# PassiveLPG.net
KiCad netlist of a schematic drawn in EAGLE
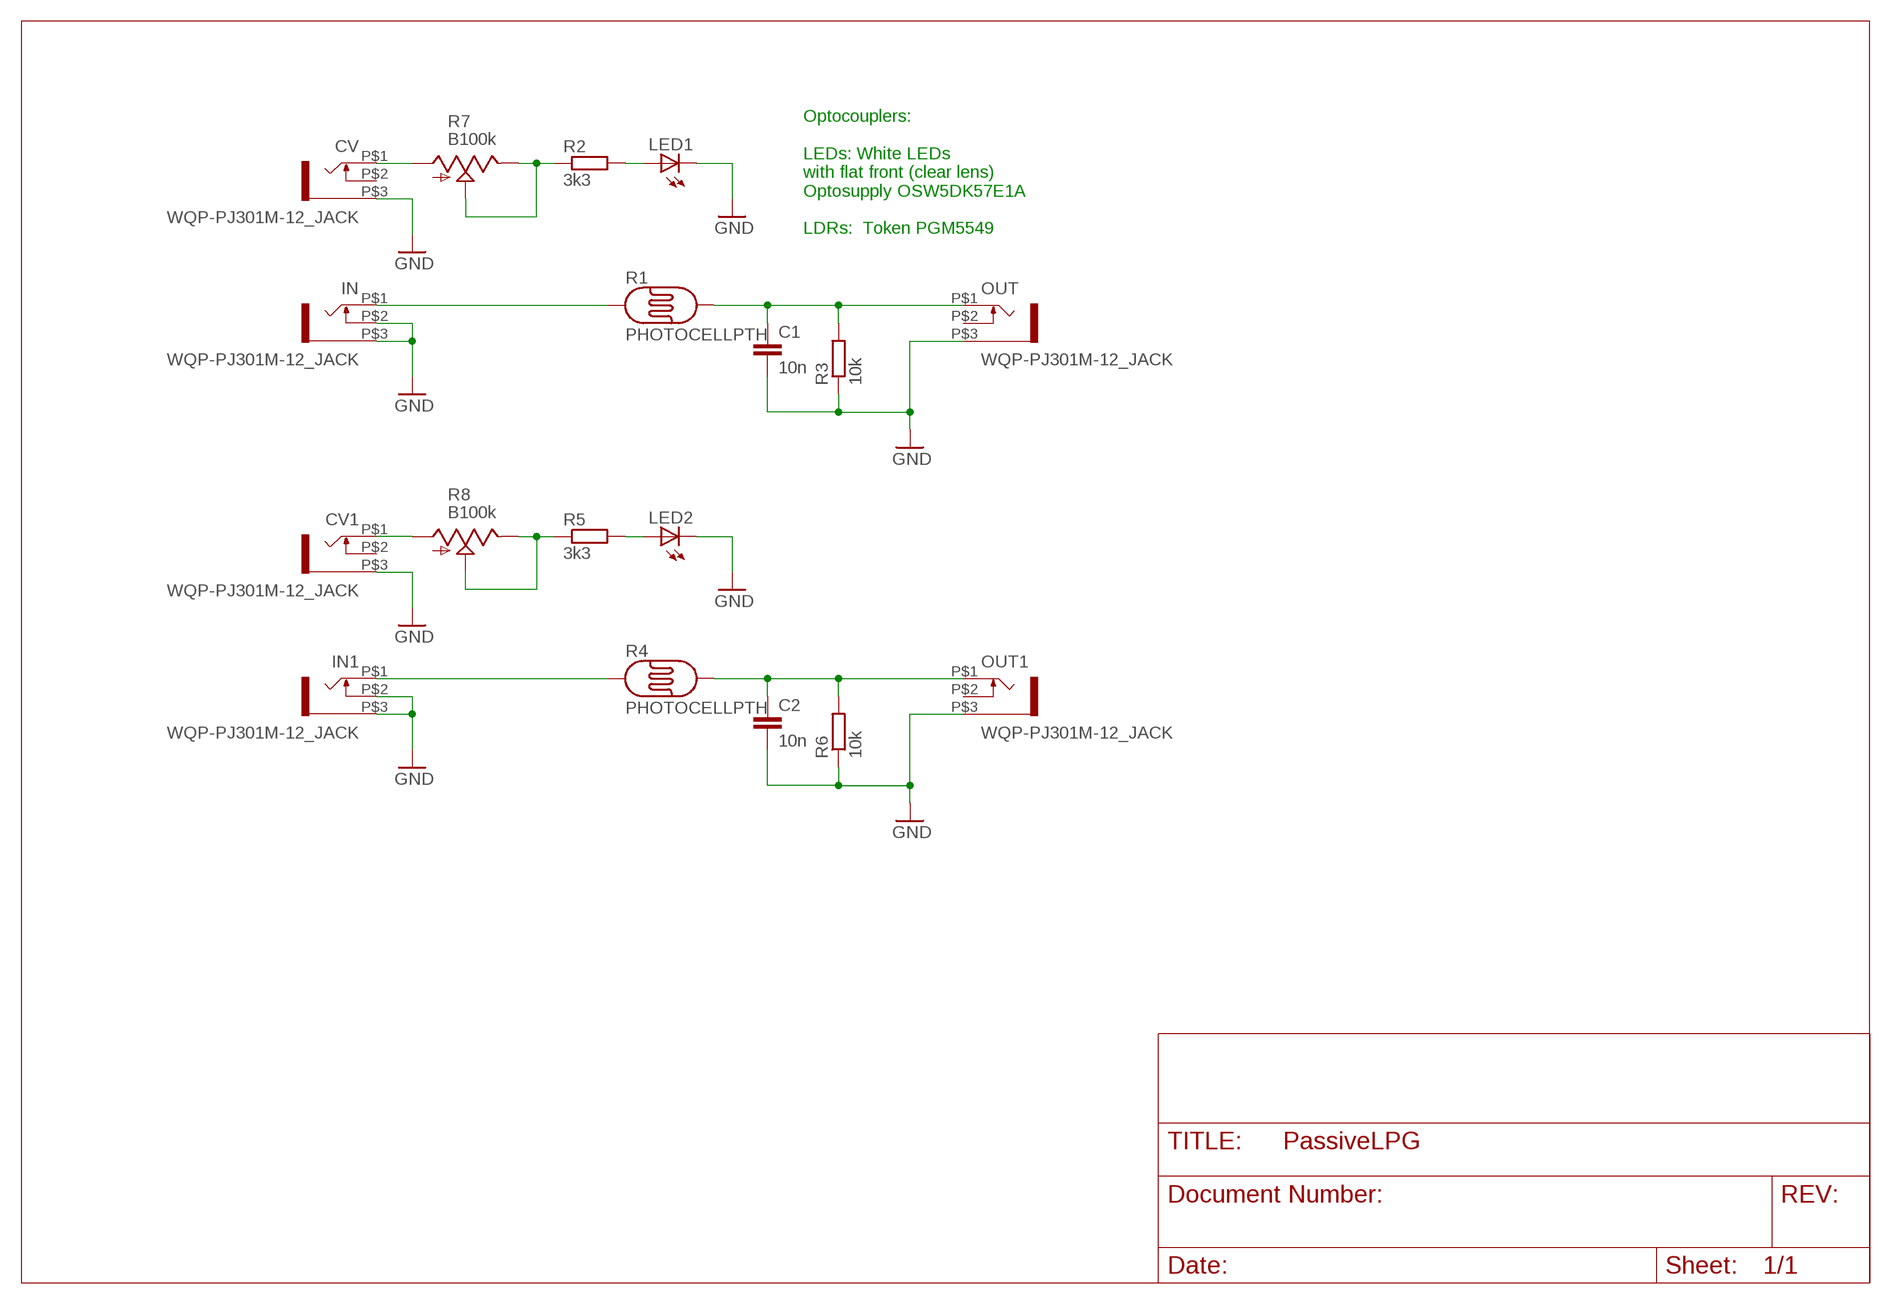
[diagram p0: schematic, sheet 1]

(export (version "E")
  (design (tool "Eeschema 10.0.6"))
  (components
    (comp (ref "C1")
      (value "10n")
      (footprint "eagle-import:C050-025X075")
      (libsource (lib "eagle-import") (part "C-EU050-025X075"))
    )
    (comp (ref "C2")
      (value "10n")
      (footprint "eagle-import:C050-025X075")
      (libsource (lib "eagle-import") (part "C-EU050-025X075"))
    )
    (comp (ref "CV")
      (value "WQP-PJ301M-12_JACK")
      (footprint "eagle-import:WQP-PJ301M-12_JACK")
      (libsource (lib "eagle-import") (part "WQP-PJ301M-12_JACK"))
    )
    (comp (ref "CV1")
      (value "WQP-PJ301M-12_JACK")
      (footprint "eagle-import:WQP-PJ301M-12_JACK")
      (libsource (lib "eagle-import") (part "WQP-PJ301M-12_JACK"))
    )
    (comp (ref "IN")
      (value "WQP-PJ301M-12_JACK")
      (footprint "eagle-import:WQP-PJ301M-12_JACK")
      (libsource (lib "eagle-import") (part "WQP-PJ301M-12_JACK"))
    )
    (comp (ref "IN1")
      (value "WQP-PJ301M-12_JACK")
      (footprint "eagle-import:WQP-PJ301M-12_JACK")
      (libsource (lib "eagle-import") (part "WQP-PJ301M-12_JACK"))
    )
    (comp (ref "LED1")
      (value "LED5MM")
      (footprint "eagle-import:LED5MM")
      (libsource (lib "eagle-import") (part "LED5MM"))
    )
    (comp (ref "LED2")
      (value "LED5MM")
      (footprint "eagle-import:LED5MM")
      (libsource (lib "eagle-import") (part "LED5MM"))
    )
    (comp (ref "OUT")
      (value "WQP-PJ301M-12_JACK")
      (footprint "eagle-import:WQP-PJ301M-12_JACK")
      (libsource (lib "eagle-import") (part "WQP-PJ301M-12_JACK"))
    )
    (comp (ref "OUT1")
      (value "WQP-PJ301M-12_JACK")
      (footprint "eagle-import:WQP-PJ301M-12_JACK")
      (libsource (lib "eagle-import") (part "WQP-PJ301M-12_JACK"))
    )
    (comp (ref "R1")
      (value "PHOTOCELLPTH")
      (footprint "eagle-import:PHOTOCELL")
      (libsource (lib "eagle-import") (part "PHOTOCELLPTH"))
    )
    (comp (ref "R2")
      (value "3k3")
      (footprint "eagle-import:0207_7")
      (libsource (lib "eagle-import") (part "R-EU_0207/7"))
    )
    (comp (ref "R3")
      (value "10k")
      (footprint "eagle-import:0207_7")
      (libsource (lib "eagle-import") (part "R-EU_0207/7"))
    )
    (comp (ref "R4")
      (value "PHOTOCELLPTH")
      (footprint "eagle-import:PHOTOCELL")
      (libsource (lib "eagle-import") (part "PHOTOCELLPTH"))
    )
    (comp (ref "R5")
      (value "3k3")
      (footprint "eagle-import:0207_7")
      (libsource (lib "eagle-import") (part "R-EU_0207/7"))
    )
    (comp (ref "R6")
      (value "10k")
      (footprint "eagle-import:0207_7")
      (libsource (lib "eagle-import") (part "R-EU_0207/7"))
    )
    (comp (ref "R7")
      (value "B100k")
      (footprint "eagle-import:ALPS_POT_VERTICAL")
      (libsource (lib "eagle-import") (part "POT_USVERTICAL"))
    )
    (comp (ref "R8")
      (value "B100k")
      (footprint "eagle-import:ALPS_POT_VERTICAL")
      (libsource (lib "eagle-import") (part "POT_USVERTICAL"))
    )
  )
  (nets
    (net (code "1") (name "GND") (class "Default")
      (node (ref "C1") (pin "2") (pinfunction "2_2") (pintype "passive"))
      (node (ref "C2") (pin "2") (pinfunction "2_2") (pintype "passive"))
      (node (ref "CV") (pin "P$3") (pinfunction "1_P$3") (pintype "passive"))
      (node (ref "CV1") (pin "P$3") (pinfunction "1_P$3") (pintype "passive"))
      (node (ref "IN") (pin "P$2") (pinfunction "3_P$2") (pintype "passive"))
      (node (ref "IN") (pin "P$3") (pinfunction "1_P$3") (pintype "passive"))
      (node (ref "IN1") (pin "P$2") (pinfunction "3_P$2") (pintype "passive"))
      (node (ref "IN1") (pin "P$3") (pinfunction "1_P$3") (pintype "passive"))
      (node (ref "LED1") (pin "K") (pinfunction "C_K") (pintype "passive"))
      (node (ref "LED2") (pin "K") (pinfunction "C_K") (pintype "passive"))
      (node (ref "OUT") (pin "P$3") (pinfunction "1_P$3") (pintype "passive"))
      (node (ref "OUT1") (pin "P$3") (pinfunction "1_P$3") (pintype "passive"))
      (node (ref "R3") (pin "1") (pinfunction "1_1") (pintype "passive"))
      (node (ref "R6") (pin "1") (pinfunction "1_1") (pintype "passive"))
    )
    (net (code "2") (name "Net-(CV-2)") (class "Default")
      (node (ref "CV") (pin "P$1") (pinfunction "2_P$1") (pintype "passive"))
      (node (ref "R7") (pin "P$3") (pinfunction "A_P$3") (pintype "passive"))
    )
    (net (code "3") (name "Net-(CV1-2)") (class "Default")
      (node (ref "CV1") (pin "P$1") (pinfunction "2_P$1") (pintype "passive"))
      (node (ref "R8") (pin "P$3") (pinfunction "A_P$3") (pintype "passive"))
    )
    (net (code "4") (name "Net-(IN-2)") (class "Default")
      (node (ref "IN") (pin "P$1") (pinfunction "2_P$1") (pintype "passive"))
      (node (ref "R1") (pin "1") (pinfunction "P$1_1") (pintype "bidirectional"))
    )
    (net (code "5") (name "Net-(IN1-2)") (class "Default")
      (node (ref "IN1") (pin "P$1") (pinfunction "2_P$1") (pintype "passive"))
      (node (ref "R4") (pin "1") (pinfunction "P$1_1") (pintype "bidirectional"))
    )
    (net (code "6") (name "Net-(LED1-PadA)") (class "Default")
      (node (ref "LED1") (pin "A") (pinfunction "A_A") (pintype "passive"))
      (node (ref "R2") (pin "2") (pinfunction "2_2") (pintype "passive"))
    )
    (net (code "7") (name "Net-(LED2-PadA)") (class "Default")
      (node (ref "LED2") (pin "A") (pinfunction "A_A") (pintype "passive"))
      (node (ref "R5") (pin "2") (pinfunction "2_2") (pintype "passive"))
    )
    (net (code "8") (name "Net-(OUT-2)") (class "Default")
      (node (ref "C1") (pin "1") (pinfunction "1_1") (pintype "passive"))
      (node (ref "OUT") (pin "P$1") (pinfunction "2_P$1") (pintype "passive"))
      (node (ref "R1") (pin "2") (pinfunction "P$2_2") (pintype "bidirectional"))
      (node (ref "R3") (pin "2") (pinfunction "2_2") (pintype "passive"))
    )
    (net (code "9") (name "Net-(OUT1-2)") (class "Default")
      (node (ref "C2") (pin "1") (pinfunction "1_1") (pintype "passive"))
      (node (ref "OUT1") (pin "P$1") (pinfunction "2_P$1") (pintype "passive"))
      (node (ref "R4") (pin "2") (pinfunction "P$2_2") (pintype "bidirectional"))
      (node (ref "R6") (pin "2") (pinfunction "2_2") (pintype "passive"))
    )
    (net (code "10") (name "Net-(R7-E)") (class "Default")
      (node (ref "R2") (pin "1") (pinfunction "1_1") (pintype "passive"))
      (node (ref "R7") (pin "P$1") (pinfunction "E_P$1") (pintype "passive"))
      (node (ref "R7") (pin "P$2") (pinfunction "S_P$2") (pintype "passive"))
    )
    (net (code "11") (name "Net-(R8-E)") (class "Default")
      (node (ref "R5") (pin "1") (pinfunction "1_1") (pintype "passive"))
      (node (ref "R8") (pin "P$1") (pinfunction "E_P$1") (pintype "passive"))
      (node (ref "R8") (pin "P$2") (pinfunction "S_P$2") (pintype "passive"))
    )
    (net (code "12") (name "unconnected-(CV-3-PadP$2)") (class "Default")
      (node (ref "CV") (pin "P$2") (pinfunction "3_P$2") (pintype "passive"))
    )
    (net (code "13") (name "unconnected-(CV1-3-PadP$2)") (class "Default")
      (node (ref "CV1") (pin "P$2") (pinfunction "3_P$2") (pintype "passive"))
    )
    (net (code "14") (name "unconnected-(OUT-3-PadP$2)") (class "Default")
      (node (ref "OUT") (pin "P$2") (pinfunction "3_P$2") (pintype "passive"))
    )
    (net (code "15") (name "unconnected-(OUT1-3-PadP$2)") (class "Default")
      (node (ref "OUT1") (pin "P$2") (pinfunction "3_P$2") (pintype "passive"))
    )
  )
)
